# CM5_HighSpeed.net
KiCad netlist of a schematic drawn in Altium Designer
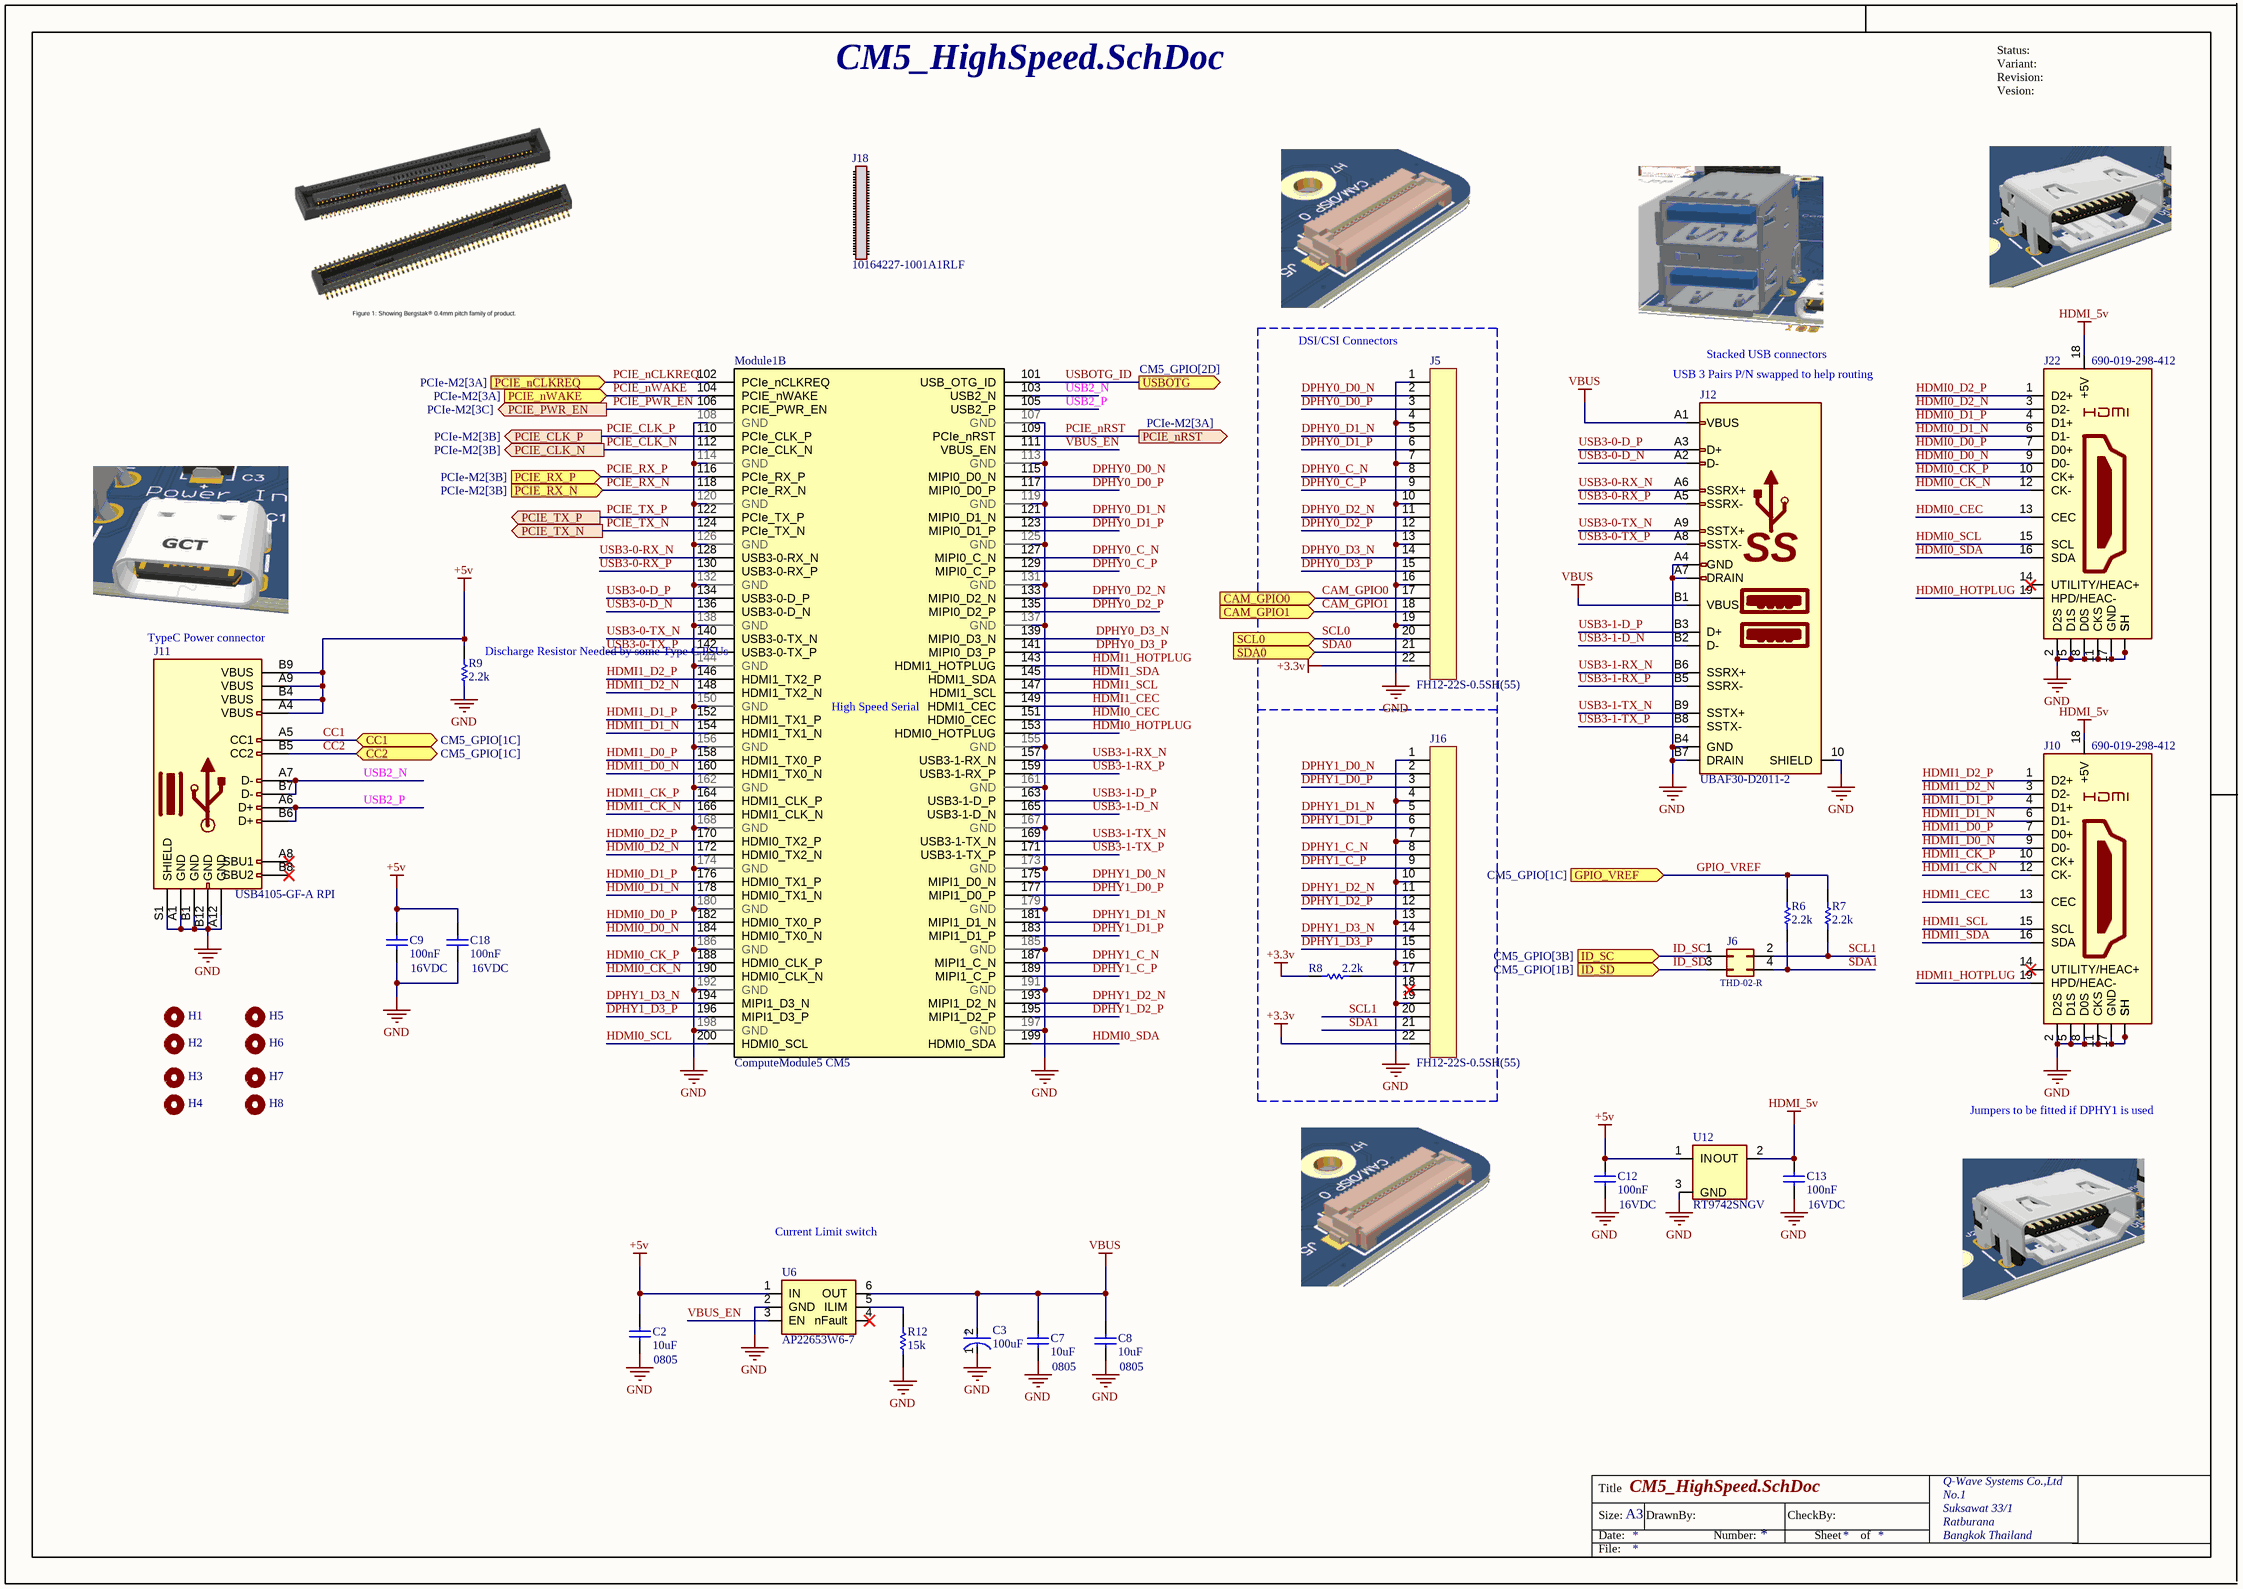
[diagram p0: CM5_HighSpeed.SchDoc]

(export (version "E")
  (design (tool "Eeschema 10.0.6"))
  (components
    (comp (ref "C2")
      (value "10uF")
      (footprint "WCAP-CSGP_0805_H=1.25mm")
      (description "WCAP-CSGP Multilayer Ceramic Chip Capacitor, General Purpose, size 0805, X5R, 10uF, 16V")
      (fields
        (field (name "MANUFACTURER") "Wurth Elektronik")
        (field (name "MANUFACTURER PART NUMBER") "885012107014")
        (field (name "SIZE") "0805")
      )
      (libsource (lib "Q-WAVE SYSTEMS CO") (part "Symbol"))
    )
    (comp (ref "C3")
      (value "100uF")
      (footprint "FP-CX-MFG")
      (description "Cap Aluminum 100uF 6.3V 20% (7.3 X 4.3 X 1.9mm) SMD 0.015 Ohm 2700mA 1000h 105C Embossed T/R")
      (fields (field (name "TOLERANCE") "20%") (field (name "VOLTAGE") "6.3V"))
      (libsource (lib "Q-WAVE SYSTEMS CO") (part "EEF-CX0J101R"))
    )
    (comp (ref "C7")
      (value "10uF")
      (footprint "WCAP-CSGP_0805_H=1.25mm")
      (description "WCAP-CSGP Multilayer Ceramic Chip Capacitor, General Purpose, size 0805, X5R, 10uF, 16V")
      (fields
        (field (name "MANUFACTURER") "Wurth Elektronik")
        (field (name "MANUFACTURER PART NUMBER") "885012107014")
        (field (name "SIZE") "0805")
      )
      (libsource (lib "Q-WAVE SYSTEMS CO") (part "Symbol"))
    )
    (comp (ref "C8")
      (value "10uF")
      (footprint "WCAP-CSGP_0805_H=1.25mm")
      (description "WCAP-CSGP Multilayer Ceramic Chip Capacitor, General Purpose, size 0805, X5R, 10uF, 16V")
      (fields
        (field (name "MANUFACTURER") "Wurth Elektronik")
        (field (name "MANUFACTURER PART NUMBER") "885012107014")
        (field (name "SIZE") "0805")
      )
      (libsource (lib "Q-WAVE SYSTEMS CO") (part "Symbol"))
    )
    (comp (ref "C9")
      (value "100nF")
      (footprint "WCAP-CSGP_0402_H=0.5mm")
      (description "WCAP-CSGP Multilayer Ceramic Chip Capacitor, General Purpose, size 0402, X5R, 100nF, 16V")
      (fields
        (field (name "MANUFACTURER PART NUMBER") "885012105016")
        (field (name "MANUFACTURER") "Wurth Elektronik")
        (field (name "RATED VOLTAGE") "16VDC")
      )
      (libsource (lib "Q-WAVE SYSTEMS CO") (part "Symbol"))
    )
    (comp (ref "C12")
      (value "100nF")
      (footprint "WCAP-CSGP_0402_H=0.5mm")
      (description "WCAP-CSGP Multilayer Ceramic Chip Capacitor, General Purpose, size 0402, X5R, 100nF, 16V")
      (fields
        (field (name "MANUFACTURER PART NUMBER") "885012105016")
        (field (name "MANUFACTURER") "Wurth Elektronik")
        (field (name "RATED VOLTAGE") "16VDC")
      )
      (libsource (lib "Q-WAVE SYSTEMS CO") (part "Symbol"))
    )
    (comp (ref "C13")
      (value "100nF")
      (footprint "WCAP-CSGP_0402_H=0.5mm")
      (description "WCAP-CSGP Multilayer Ceramic Chip Capacitor, General Purpose, size 0402, X5R, 100nF, 16V")
      (fields
        (field (name "MANUFACTURER PART NUMBER") "885012105016")
        (field (name "MANUFACTURER") "Wurth Elektronik")
        (field (name "RATED VOLTAGE") "16VDC")
      )
      (libsource (lib "Q-WAVE SYSTEMS CO") (part "Symbol"))
    )
    (comp (ref "C18")
      (value "100nF")
      (footprint "WCAP-CSGP_0402_H=0.5mm")
      (description "WCAP-CSGP Multilayer Ceramic Chip Capacitor, General Purpose, size 0402, X5R, 100nF, 16V")
      (fields
        (field (name "MANUFACTURER PART NUMBER") "885012105016")
        (field (name "MANUFACTURER") "Wurth Elektronik")
        (field (name "RATED VOLTAGE") "16VDC")
      )
      (libsource (lib "Q-WAVE SYSTEMS CO") (part "Symbol"))
    )
    (comp (ref "H1")
      (value "MountingHole CMIO")
      (footprint "MountingHole CMIO")
      (libsource (lib "Q-WAVE SYSTEMS CO") (part "MountingHole CMIO"))
    )
    (comp (ref "H2")
      (value "MountingHole CMIO")
      (footprint "MountingHole CMIO")
      (libsource (lib "Q-WAVE SYSTEMS CO") (part "MountingHole CMIO"))
    )
    (comp (ref "H3")
      (value "MountingHole CMIO")
      (footprint "MountingHole CMIO")
      (libsource (lib "Q-WAVE SYSTEMS CO") (part "MountingHole CMIO"))
    )
    (comp (ref "H4")
      (value "MountingHole CMIO")
      (footprint "MountingHole CMIO")
      (libsource (lib "Q-WAVE SYSTEMS CO") (part "MountingHole CMIO"))
    )
    (comp (ref "H5")
      (value "MountingHole CMIO")
      (footprint "MountingHole CMIO")
      (libsource (lib "Q-WAVE SYSTEMS CO") (part "MountingHole CMIO"))
    )
    (comp (ref "H6")
      (value "MountingHole CMIO")
      (footprint "MountingHole CMIO")
      (libsource (lib "Q-WAVE SYSTEMS CO") (part "MountingHole CMIO"))
    )
    (comp (ref "H7")
      (value "MountingHole CMIO")
      (footprint "MountingHole CMIO")
      (libsource (lib "Q-WAVE SYSTEMS CO") (part "MountingHole CMIO"))
    )
    (comp (ref "H8")
      (value "MountingHole CMIO")
      (footprint "MountingHole CMIO")
      (libsource (lib "Q-WAVE SYSTEMS CO") (part "MountingHole CMIO"))
    )
    (comp (ref "J5")
      (value "FH12-22S-0.5SH(55)")
      (footprint "FH12-22S-0.5SH(55)")
      (description "Connectors for Connecting - 0.5/1-mm Pitch FPC/FFC - FH12 Series (HIROSE ELECTRIC)")
      (libsource (lib "Q-WAVE SYSTEMS CO") (part "FH12-22S-0.5SH(55)"))
    )
    (comp (ref "J6")
      (value "THD-02-R")
      (footprint "THD-02-R")
      (description "PinHeader 2x02 P2.54mm Vertical")
      (fields
        (field (name "MANUFACTURER") "Wurth Elektronik")
        (field (name "MANUFACTURER PART NUMBER") "61300421121")
      )
      (libsource (lib "Q-WAVE SYSTEMS CO") (part "THD-02-R"))
    )
    (comp (ref "J10")
      (value "690-019-298-412")
      (footprint "690-019-298-412")
      (description "Connector: HDMI; socket; PIN: 19; gold-plated; Body coating: tinned")
      (libsource (lib "Q-WAVE SYSTEMS CO") (part "690-019-298-412"))
    )
    (comp (ref "J11")
      (value "USB4105-GF-A RPI")
      (footprint "USB4105-GF-A RPI")
      (description "Conn USB 2.0 Type C RCP 24 POS 0.3mm/0.5mm Solder RA SMD 24 Terminal 1 Port T/R")
      (libsource (lib "Q-WAVE SYSTEMS CO") (part "USB4105-GF-A RPI"))
    )
    (comp (ref "J12")
      (value "UBAF30-D2011-2")
      (footprint "UBAF30-D2011-2")
      (description "Conn USB 3.0 Type A RCP 18 POS 2mm/2mm Solder RA Thru-Hole 18 Terminal 2 Port T/R")
      (libsource (lib "Q-WAVE SYSTEMS CO") (part "UBAF30-D2011-2"))
    )
    (comp (ref "J16")
      (value "FH12-22S-0.5SH(55)")
      (footprint "FH12-22S-0.5SH(55)")
      (description "Connectors for Connecting - 0.5/1-mm Pitch FPC/FFC - FH12 Series (HIROSE ELECTRIC)")
      (libsource (lib "Q-WAVE SYSTEMS CO") (part "FH12-22S-0.5SH(55)"))
    )
    (comp (ref "J18")
      (value "10164227-1001A1RLF")
      (footprint "CM5-BergStak-10164227")
      (description "CM5 1.5mm Height 0.4MM Btb, 100P, Receptacle, 1.5MM Stack Height")
      (libsource (lib "Q-WAVE SYSTEMS CO") (part "10164227-1001A1RLF"))
    )
    (comp (ref "J22")
      (value "690-019-298-412")
      (footprint "690-019-298-412")
      (description "Connector: HDMI; socket; PIN: 19; gold-plated; Body coating: tinned")
      (libsource (lib "Q-WAVE SYSTEMS CO") (part "690-019-298-412"))
    )
    (comp (ref "Module1")
      (value "ComputeModule5 CM5")
      (footprint "ComputeModule5-CM5")
      (description "Raspberry Pi Compute Module 5")
      (libsource (lib "Q-WAVE SYSTEMS CO") (part "ComputeModule5-CM5"))
    )
    (comp (ref "R6")
      (value "2.2k")
      (footprint "SMD-0402-RES")
      (description "RES SMD 2.2K OHM 1% 1/10W 0402")
      (fields (field (name "TOLERANCE") "±1%") (field (name "PART NUMBER") "ERJ-2RKF2201X"))
      (libsource (lib "Q-WAVE SYSTEMS CO") (part "resistor"))
    )
    (comp (ref "R7")
      (value "2.2k")
      (footprint "SMD-0402-RES")
      (description "RES SMD 2.2K OHM 1% 1/10W 0402")
      (fields (field (name "TOLERANCE") "±1%") (field (name "PART NUMBER") "ERJ-2RKF2201X"))
      (libsource (lib "Q-WAVE SYSTEMS CO") (part "resistor"))
    )
    (comp (ref "R8")
      (value "2.2k")
      (footprint "SMD-0402-RES")
      (description "RES SMD 2.2K OHM 1% 1/10W 0402")
      (fields (field (name "TOLERANCE") "±1%") (field (name "PART NUMBER") "ERJ-2RKF2201X"))
      (libsource (lib "Q-WAVE SYSTEMS CO") (part "resistor"))
    )
    (comp (ref "R9")
      (value "2.2k")
      (footprint "SMD-0402-RES")
      (description "RES SMD 2.2K OHM 1% 1/10W 0402")
      (fields (field (name "TOLERANCE") "±1%") (field (name "PART NUMBER") "ERJ-2RKF2201X"))
      (libsource (lib "Q-WAVE SYSTEMS CO") (part "resistor"))
    )
    (comp (ref "R12")
      (value "15k")
      (footprint "SMD-0402-RES")
      (description "RES SMD 15K OHM 1% 1/10W 0402")
      (fields
        (field (name "DIGI-KEY PART NUMBER") "P15.0KLCT-ND")
        (field (name "PART NUMBER") "ERJ-2RKF1502X")
      )
      (libsource (lib "Q-WAVE SYSTEMS CO") (part "resistor"))
    )
    (comp (ref "U6")
      (value "AP22653W6-7")
      (footprint "FP-SOT26-IPC_A")
      (description "USB Power High Side Switch Single 3V to 5.5V 2.1A 6-Pin SOT-26 T/R")
      (libsource (lib "Q-WAVE SYSTEMS CO") (part "AP22653W6-7"))
    )
    (comp (ref "U12")
      (value "RT9742SNGV")
      (footprint "RT9742SNGV")
      (description "IC Pwr Switch N-chan 1: 1 SOT23-3")
      (libsource (lib "Q-WAVE SYSTEMS CO") (part "RT9742SNGV"))
    )
  )
  (nets
    (net (code "1") (name "+3.3v") (class "Default")
      (node (ref "J16") (pin "22") (pinfunction "Pin_22_22") (pintype "passive"))
      (node (ref "J5") (pin "22") (pinfunction "Pin_22_22") (pintype "passive"))
      (node (ref "R8") (pin "1") (pinfunction "1_1") (pintype "passive"))
    )
    (net (code "2") (name "+5v") (class "Default")
      (node (ref "C12") (pin "2") (pinfunction "2_2") (pintype "passive"))
      (node (ref "C18") (pin "2") (pinfunction "2_2") (pintype "passive"))
      (node (ref "C2") (pin "2") (pinfunction "2_2") (pintype "passive"))
      (node (ref "C9") (pin "2") (pinfunction "2_2") (pintype "passive"))
      (node (ref "J11") (pin "A4") (pinfunction "VBUS_A4") (pintype "passive"))
      (node (ref "J11") (pin "A9") (pinfunction "VBUS_A9") (pintype "passive"))
      (node (ref "J11") (pin "B4") (pinfunction "VBUS_B4") (pintype "passive"))
      (node (ref "J11") (pin "B9") (pinfunction "VBUS_B9") (pintype "passive"))
      (node (ref "R9") (pin "2") (pinfunction "2_2") (pintype "passive"))
      (node (ref "U12") (pin "1") (pinfunction "IN_1") (pintype "passive"))
      (node (ref "U6") (pin "1") (pinfunction "IN_1") (pintype "passive"))
    )
    (net (code "3") (name "/CAM_GPIO0") (class "Default")
      (node (ref "J5") (pin "17") (pinfunction "Pin_17_17") (pintype "passive"))
    )
    (net (code "4") (name "/CAM_GPIO1") (class "Default")
      (node (ref "J5") (pin "18") (pinfunction "Pin_18_18") (pintype "passive"))
    )
    (net (code "5") (name "/CC1") (class "Default")
      (node (ref "J11") (pin "A5") (pinfunction "CC1_A5") (pintype "passive"))
    )
    (net (code "6") (name "/CC2") (class "Default")
      (node (ref "J11") (pin "B5") (pinfunction "CC2_B5") (pintype "passive"))
    )
    (net (code "7") (name "/DPHY0_C_N") (class "Default")
      (node (ref "J5") (pin "8") (pinfunction "Pin_8_8") (pintype "passive"))
      (node (ref "Module1") (pin "127") (pinfunction "MIPI0_C_N_127") (pintype "passive"))
    )
    (net (code "8") (name "/DPHY0_C_P") (class "Default")
      (node (ref "J5") (pin "9") (pinfunction "Pin_9_9") (pintype "passive"))
      (node (ref "Module1") (pin "129") (pinfunction "MIPI0_C_P_129") (pintype "passive"))
    )
    (net (code "9") (name "/DPHY0_D0_N") (class "Default")
      (node (ref "J5") (pin "2") (pinfunction "Pin_2_2") (pintype "passive"))
      (node (ref "Module1") (pin "115") (pinfunction "MIPI0_D0_N_115") (pintype "passive"))
    )
    (net (code "10") (name "/DPHY0_D0_P") (class "Default")
      (node (ref "J5") (pin "3") (pinfunction "Pin_3_3") (pintype "passive"))
      (node (ref "Module1") (pin "117") (pinfunction "MIPI0_D0_P_117") (pintype "passive"))
    )
    (net (code "11") (name "/DPHY0_D1_N") (class "Default")
      (node (ref "J5") (pin "5") (pinfunction "Pin_5_5") (pintype "passive"))
      (node (ref "Module1") (pin "121") (pinfunction "MIPI0_D1_N_121") (pintype "passive"))
    )
    (net (code "12") (name "/DPHY0_D1_P") (class "Default")
      (node (ref "J5") (pin "6") (pinfunction "Pin_6_6") (pintype "passive"))
      (node (ref "Module1") (pin "123") (pinfunction "MIPI0_D1_P_123") (pintype "passive"))
    )
    (net (code "13") (name "/DPHY0_D2_N") (class "Default")
      (node (ref "J5") (pin "11") (pinfunction "Pin_11_11") (pintype "passive"))
      (node (ref "Module1") (pin "133") (pinfunction "MIPI0_D2_N_133") (pintype "passive"))
    )
    (net (code "14") (name "/DPHY0_D2_P") (class "Default")
      (node (ref "J5") (pin "12") (pinfunction "Pin_12_12") (pintype "passive"))
      (node (ref "Module1") (pin "135") (pinfunction "MIPI0_D2_P_135") (pintype "passive"))
    )
    (net (code "15") (name "/DPHY0_D3_N") (class "Default")
      (node (ref "J5") (pin "14") (pinfunction "Pin_14_14") (pintype "passive"))
      (node (ref "Module1") (pin "139") (pinfunction "MIPI0_D3_N_139") (pintype "passive"))
    )
    (net (code "16") (name "/DPHY0_D3_P") (class "Default")
      (node (ref "J5") (pin "15") (pinfunction "Pin_15_15") (pintype "passive"))
      (node (ref "Module1") (pin "141") (pinfunction "MIPI0_D3_P_141") (pintype "passive"))
    )
    (net (code "17") (name "/DPHY1_C_N") (class "Default")
      (node (ref "J16") (pin "8") (pinfunction "Pin_8_8") (pintype "passive"))
      (node (ref "Module1") (pin "187") (pinfunction "MIPI1_C_N_187") (pintype "passive"))
    )
    (net (code "18") (name "/DPHY1_C_P") (class "Default")
      (node (ref "J16") (pin "9") (pinfunction "Pin_9_9") (pintype "passive"))
      (node (ref "Module1") (pin "189") (pinfunction "MIPI1_C_P_189") (pintype "passive"))
    )
    (net (code "19") (name "/DPHY1_D0_N") (class "Default")
      (node (ref "J16") (pin "2") (pinfunction "Pin_2_2") (pintype "passive"))
      (node (ref "Module1") (pin "175") (pinfunction "MIPI1_D0_N_175") (pintype "passive"))
    )
    (net (code "20") (name "/DPHY1_D0_P") (class "Default")
      (node (ref "J16") (pin "3") (pinfunction "Pin_3_3") (pintype "passive"))
      (node (ref "Module1") (pin "177") (pinfunction "MIPI1_D0_P_177") (pintype "passive"))
    )
    (net (code "21") (name "/DPHY1_D1_N") (class "Default")
      (node (ref "J16") (pin "5") (pinfunction "Pin_5_5") (pintype "passive"))
      (node (ref "Module1") (pin "181") (pinfunction "MIPI1_D1_N_181") (pintype "passive"))
    )
    (net (code "22") (name "/DPHY1_D1_P") (class "Default")
      (node (ref "J16") (pin "6") (pinfunction "Pin_6_6") (pintype "passive"))
      (node (ref "Module1") (pin "183") (pinfunction "MIPI1_D1_P_183") (pintype "passive"))
    )
    (net (code "23") (name "/DPHY1_D2_N") (class "Default")
      (node (ref "J16") (pin "11") (pinfunction "Pin_11_11") (pintype "passive"))
      (node (ref "Module1") (pin "193") (pinfunction "MIPI1_D2_N_193") (pintype "passive"))
    )
    (net (code "24") (name "/DPHY1_D2_P") (class "Default")
      (node (ref "J16") (pin "12") (pinfunction "Pin_12_12") (pintype "passive"))
      (node (ref "Module1") (pin "195") (pinfunction "MIPI1_D2_P_195") (pintype "passive"))
    )
    (net (code "25") (name "/DPHY1_D3_N") (class "Default")
      (node (ref "J16") (pin "14") (pinfunction "Pin_14_14") (pintype "passive"))
      (node (ref "Module1") (pin "194") (pinfunction "MIPI1_D3_N_194") (pintype "passive"))
    )
    (net (code "26") (name "/DPHY1_D3_P") (class "Default")
      (node (ref "J16") (pin "15") (pinfunction "Pin_15_15") (pintype "passive"))
      (node (ref "Module1") (pin "196") (pinfunction "MIPI1_D3_P_196") (pintype "passive"))
    )
    (net (code "27") (name "/GPIO_VREF") (class "Default")
      (node (ref "R6") (pin "2") (pinfunction "2_2") (pintype "passive"))
      (node (ref "R7") (pin "2") (pinfunction "2_2") (pintype "passive"))
    )
    (net (code "28") (name "/HDMI0_CEC") (class "Default")
      (node (ref "J22") (pin "13") (pinfunction "CEC_13") (pintype "passive"))
      (node (ref "Module1") (pin "151") (pinfunction "HDMI0_CEC_151") (pintype "passive"))
    )
    (net (code "29") (name "/HDMI0_CK_N") (class "Default")
      (node (ref "J22") (pin "12") (pinfunction "CK-_12") (pintype "passive"))
      (node (ref "Module1") (pin "190") (pinfunction "HDMI0_CLK_N_190") (pintype "passive"))
    )
    (net (code "30") (name "/HDMI0_CK_P") (class "Default")
      (node (ref "J22") (pin "10") (pinfunction "CK+_10") (pintype "passive"))
      (node (ref "Module1") (pin "188") (pinfunction "HDMI0_CLK_P_188") (pintype "passive"))
    )
    (net (code "31") (name "/HDMI0_D0_N") (class "Default")
      (node (ref "J22") (pin "9") (pinfunction "D0-_9") (pintype "passive"))
      (node (ref "Module1") (pin "184") (pinfunction "HDMI0_TX0_N_184") (pintype "passive"))
    )
    (net (code "32") (name "/HDMI0_D0_P") (class "Default")
      (node (ref "J22") (pin "7") (pinfunction "D0+_7") (pintype "passive"))
      (node (ref "Module1") (pin "182") (pinfunction "HDMI0_TX0_P_182") (pintype "passive"))
    )
    (net (code "33") (name "/HDMI0_D1_N") (class "Default")
      (node (ref "J22") (pin "6") (pinfunction "D1-_6") (pintype "passive"))
      (node (ref "Module1") (pin "178") (pinfunction "HDMI0_TX1_N_178") (pintype "passive"))
    )
    (net (code "34") (name "/HDMI0_D1_P") (class "Default")
      (node (ref "J22") (pin "4") (pinfunction "D1+_4") (pintype "passive"))
      (node (ref "Module1") (pin "176") (pinfunction "HDMI0_TX1_P_176") (pintype "passive"))
    )
    (net (code "35") (name "/HDMI0_D2_N") (class "Default")
      (node (ref "J22") (pin "3") (pinfunction "D2-_3") (pintype "passive"))
      (node (ref "Module1") (pin "172") (pinfunction "HDMI0_TX2_N_172") (pintype "passive"))
    )
    (net (code "36") (name "/HDMI0_D2_P") (class "Default")
      (node (ref "J22") (pin "1") (pinfunction "D2+_1") (pintype "passive"))
      (node (ref "Module1") (pin "170") (pinfunction "HDMI0_TX2_P_170") (pintype "passive"))
    )
    (net (code "37") (name "/HDMI0_HOTPLUG") (class "Default")
      (node (ref "J22") (pin "19") (pinfunction "HPD/HEAC-_19") (pintype "passive"))
      (node (ref "Module1") (pin "153") (pinfunction "HDMI0_HOTPLUG_153") (pintype "passive"))
    )
    (net (code "38") (name "/HDMI0_SCL") (class "Default")
      (node (ref "J22") (pin "15") (pinfunction "SCL_15") (pintype "passive"))
      (node (ref "Module1") (pin "200") (pinfunction "HDMI0_SCL_200") (pintype "passive"))
    )
    (net (code "39") (name "/HDMI0_SDA") (class "Default")
      (node (ref "J22") (pin "16") (pinfunction "SDA_16") (pintype "passive"))
      (node (ref "Module1") (pin "199") (pinfunction "HDMI0_SDA_199") (pintype "passive"))
    )
    (net (code "40") (name "/HDMI1_CEC") (class "Default")
      (node (ref "J10") (pin "13") (pinfunction "CEC_13") (pintype "passive"))
      (node (ref "Module1") (pin "149") (pinfunction "HDMI1_CEC_149") (pintype "passive"))
    )
    (net (code "41") (name "/HDMI1_CK_N") (class "Default")
      (node (ref "J10") (pin "12") (pinfunction "CK-_12") (pintype "passive"))
      (node (ref "Module1") (pin "166") (pinfunction "HDMI1_CLK_N_166") (pintype "passive"))
    )
    (net (code "42") (name "/HDMI1_CK_P") (class "Default")
      (node (ref "J10") (pin "10") (pinfunction "CK+_10") (pintype "passive"))
      (node (ref "Module1") (pin "164") (pinfunction "HDMI1_CLK_P_164") (pintype "passive"))
    )
    (net (code "43") (name "/HDMI1_D0_N") (class "Default")
      (node (ref "J10") (pin "9") (pinfunction "D0-_9") (pintype "passive"))
      (node (ref "Module1") (pin "160") (pinfunction "HDMI1_TX0_N_160") (pintype "passive"))
    )
    (net (code "44") (name "/HDMI1_D0_P") (class "Default")
      (node (ref "J10") (pin "7") (pinfunction "D0+_7") (pintype "passive"))
      (node (ref "Module1") (pin "158") (pinfunction "HDMI1_TX0_P_158") (pintype "passive"))
    )
    (net (code "45") (name "/HDMI1_D1_N") (class "Default")
      (node (ref "J10") (pin "6") (pinfunction "D1-_6") (pintype "passive"))
      (node (ref "Module1") (pin "154") (pinfunction "HDMI1_TX1_N_154") (pintype "passive"))
    )
    (net (code "46") (name "/HDMI1_D1_P") (class "Default")
      (node (ref "J10") (pin "4") (pinfunction "D1+_4") (pintype "passive"))
      (node (ref "Module1") (pin "152") (pinfunction "HDMI1_TX1_P_152") (pintype "passive"))
    )
    (net (code "47") (name "/HDMI1_D2_N") (class "Default")
      (node (ref "J10") (pin "3") (pinfunction "D2-_3") (pintype "passive"))
      (node (ref "Module1") (pin "148") (pinfunction "HDMI1_TX2_N_148") (pintype "passive"))
    )
    (net (code "48") (name "/HDMI1_D2_P") (class "Default")
      (node (ref "J10") (pin "1") (pinfunction "D2+_1") (pintype "passive"))
      (node (ref "Module1") (pin "146") (pinfunction "HDMI1_TX2_P_146") (pintype "passive"))
    )
    (net (code "49") (name "/HDMI1_HOTPLUG") (class "Default")
      (node (ref "J10") (pin "19") (pinfunction "HPD/HEAC-_19") (pintype "passive"))
      (node (ref "Module1") (pin "143") (pinfunction "HDMI1_HOTPLUG_143") (pintype "passive"))
    )
    (net (code "50") (name "/HDMI1_SCL") (class "Default")
      (node (ref "J10") (pin "15") (pinfunction "SCL_15") (pintype "passive"))
      (node (ref "Module1") (pin "147") (pinfunction "HDMI1_SCL_147") (pintype "passive"))
    )
    (net (code "51") (name "/HDMI1_SDA") (class "Default")
      (node (ref "J10") (pin "16") (pinfunction "SDA_16") (pintype "passive"))
      (node (ref "Module1") (pin "145") (pinfunction "HDMI1_SDA_145") (pintype "passive"))
    )
    (net (code "52") (name "/ID_SC") (class "Default")
      (node (ref "J6") (pin "1") (pinfunction "Pin_1_1") (pintype "passive"))
    )
    (net (code "53") (name "/ID_SD") (class "Default")
      (node (ref "J6") (pin "3") (pinfunction "Pin_3_3") (pintype "passive"))
    )
    (net (code "54") (name "/PCIE_CLK_N") (class "Default")
      (node (ref "Module1") (pin "112") (pinfunction "PCIe_CLK_N_112") (pintype "passive"))
    )
    (net (code "55") (name "/PCIE_CLK_P") (class "Default")
      (node (ref "Module1") (pin "110") (pinfunction "PCIe_CLK_P_110") (pintype "passive"))
    )
    (net (code "56") (name "/PCIE_PWR_EN") (class "Default")
      (node (ref "Module1") (pin "106") (pinfunction "PCIE_PWR_EN_106") (pintype "passive"))
    )
    (net (code "57") (name "/PCIE_RX_N") (class "Default")
      (node (ref "Module1") (pin "118") (pinfunction "PCIe_RX_N_118") (pintype "passive"))
    )
    (net (code "58") (name "/PCIE_RX_P") (class "Default")
      (node (ref "Module1") (pin "116") (pinfunction "PCIe_RX_P_116") (pintype "passive"))
    )
    (net (code "59") (name "/PCIE_TX_N") (class "Default")
      (node (ref "Module1") (pin "124") (pinfunction "PCIe_TX_N_124") (pintype "passive"))
    )
    (net (code "60") (name "/PCIE_TX_P") (class "Default")
      (node (ref "Module1") (pin "122") (pinfunction "PCIe_TX_P_122") (pintype "passive"))
    )
    (net (code "61") (name "/PCIE_nCLKREQ") (class "Default")
      (node (ref "Module1") (pin "102") (pinfunction "PCIe_nCLKREQ_102") (pintype "passive"))
    )
    (net (code "62") (name "/PCIE_nRST") (class "Default")
      (node (ref "Module1") (pin "109") (pinfunction "PCIe_nRST_109") (pintype "passive"))
    )
    (net (code "63") (name "/PCIE_nWAKE") (class "Default")
      (node (ref "Module1") (pin "104") (pinfunction "PCIE_nWAKE_104") (pintype "passive"))
    )
    (net (code "64") (name "/SCL0") (class "Default")
      (node (ref "J5") (pin "20") (pinfunction "Pin_20_20") (pintype "passive"))
    )
    (net (code "65") (name "/SCL1") (class "Default")
      (node (ref "J16") (pin "20") (pinfunction "Pin_20_20") (pintype "passive"))
      (node (ref "J6") (pin "2") (pinfunction "Pin_2_2") (pintype "passive"))
      (node (ref "R7") (pin "1") (pinfunction "1_1") (pintype "passive"))
    )
    (net (code "66") (name "/SDA0") (class "Default")
      (node (ref "J5") (pin "21") (pinfunction "Pin_21_21") (pintype "passive"))
    )
    (net (code "67") (name "/SDA1") (class "Default")
      (node (ref "J16") (pin "21") (pinfunction "Pin_21_21") (pintype "passive"))
      (node (ref "J6") (pin "4") (pinfunction "Pin_4_4") (pintype "passive"))
      (node (ref "R6") (pin "1") (pinfunction "1_1") (pintype "passive"))
    )
    (net (code "68") (name "/USB2_N") (class "Default")
      (node (ref "J11") (pin "A7") (pinfunction "D-_A7") (pintype "passive"))
      (node (ref "J11") (pin "B7") (pinfunction "D-_B7") (pintype "passive"))
      (node (ref "Module1") (pin "103") (pinfunction "USB2_N_103") (pintype "passive"))
    )
    (net (code "69") (name "/USB2_P") (class "Default")
      (node (ref "J11") (pin "A6") (pinfunction "D+_A6") (pintype "passive"))
      (node (ref "J11") (pin "B6") (pinfunction "D+_B6") (pintype "passive"))
      (node (ref "Module1") (pin "105") (pinfunction "USB2_P_105") (pintype "passive"))
    )
    (net (code "70") (name "/USB3-0-D_N") (class "Default")
      (node (ref "J12") (pin "A2") (pinfunction "D-_A2") (pintype "passive"))
      (node (ref "Module1") (pin "136") (pinfunction "USB3-0-D_N_136") (pintype "passive"))
    )
    (net (code "71") (name "/USB3-0-D_P") (class "Default")
      (node (ref "J12") (pin "A3") (pinfunction "D+_A3") (pintype "passive"))
      (node (ref "Module1") (pin "134") (pinfunction "USB3-0-D_P_134") (pintype "passive"))
    )
    (net (code "72") (name "/USB3-0-RX_N") (class "Default")
      (node (ref "J12") (pin "A6") (pinfunction "SSRX+_A6") (pintype "passive"))
      (node (ref "Module1") (pin "128") (pinfunction "USB3-0-RX_N_128") (pintype "passive"))
    )
    (net (code "73") (name "/USB3-0-RX_P") (class "Default")
      (node (ref "J12") (pin "A5") (pinfunction "SSRX-_A5") (pintype "passive"))
      (node (ref "Module1") (pin "130") (pinfunction "USB3-0-RX_P_130") (pintype "passive"))
    )
    (net (code "74") (name "/USB3-0-TX_N") (class "Default")
      (node (ref "J12") (pin "A9") (pinfunction "SSTX+_A9") (pintype "passive"))
      (node (ref "Module1") (pin "140") (pinfunction "USB3-0-TX_N_140") (pintype "passive"))
    )
    (net (code "75") (name "/USB3-0-TX_P") (class "Default")
      (node (ref "J12") (pin "A8") (pinfunction "SSTX-_A8") (pintype "passive"))
      (node (ref "Module1") (pin "142") (pinfunction "USB3-0-TX_P_142") (pintype "passive"))
    )
    (net (code "76") (name "/USB3-1-D_N") (class "Default")
      (node (ref "J12") (pin "B2") (pinfunction "D-_B2") (pintype "passive"))
      (node (ref "Module1") (pin "165") (pinfunction "USB3-1-D_N_165") (pintype "passive"))
    )
    (net (code "77") (name "/USB3-1-D_P") (class "Default")
      (node (ref "J12") (pin "B3") (pinfunction "D+_B3") (pintype "passive"))
      (node (ref "Module1") (pin "163") (pinfunction "USB3-1-D_P_163") (pintype "passive"))
    )
    (net (code "78") (name "/USB3-1-RX_N") (class "Default")
      (node (ref "J12") (pin "B6") (pinfunction "SSRX+_B6") (pintype "passive"))
      (node (ref "Module1") (pin "157") (pinfunction "USB3-1-RX_N_157") (pintype "passive"))
    )
    (net (code "79") (name "/USB3-1-RX_P") (class "Default")
      (node (ref "J12") (pin "B5") (pinfunction "SSRX-_B5") (pintype "passive"))
      (node (ref "Module1") (pin "159") (pinfunction "USB3-1-RX_P_159") (pintype "passive"))
    )
    (net (code "80") (name "/USB3-1-TX_N") (class "Default")
      (node (ref "J12") (pin "B9") (pinfunction "SSTX+_B9") (pintype "passive"))
      (node (ref "Module1") (pin "169") (pinfunction "USB3-1-TX_N_169") (pintype "passive"))
    )
    (net (code "81") (name "/USB3-1-TX_P") (class "Default")
      (node (ref "J12") (pin "B8") (pinfunction "SSTX-_B8") (pintype "passive"))
      (node (ref "Module1") (pin "171") (pinfunction "USB3-1-TX_P_171") (pintype "passive"))
    )
    (net (code "82") (name "/USBOTG_ID") (class "Default")
      (node (ref "Module1") (pin "101") (pinfunction "USB_OTG_ID_101") (pintype "passive"))
    )
    (net (code "83") (name "/VBUS_EN") (class "Default")
      (node (ref "Module1") (pin "111") (pinfunction "VBUS_EN_111") (pintype "passive"))
      (node (ref "U6") (pin "3") (pinfunction "EN_3") (pintype "passive"))
    )
    (net (code "84") (name "GND") (class "Default")
      (node (ref "C12") (pin "1") (pinfunction "1_1") (pintype "passive"))
      (node (ref "C13") (pin "1") (pinfunction "1_1") (pintype "passive"))
      (node (ref "C18") (pin "1") (pinfunction "1_1") (pintype "passive"))
      (node (ref "C2") (pin "1") (pinfunction "1_1") (pintype "passive"))
      (node (ref "C3") (pin "1") (pinfunction "C_1") (pintype "passive"))
      (node (ref "C7") (pin "1") (pinfunction "1_1") (pintype "passive"))
      (node (ref "C8") (pin "1") (pinfunction "1_1") (pintype "passive"))
      (node (ref "C9") (pin "1") (pinfunction "1_1") (pintype "passive"))
      (node (ref "J10") (pin "11") (pinfunction "CKS_11") (pintype "passive"))
      (node (ref "J10") (pin "17") (pinfunction "GND_17") (pintype "passive"))
      (node (ref "J10") (pin "2") (pinfunction "D2S_2") (pintype "passive"))
      (node (ref "J10") (pin "5") (pinfunction "D1S_5") (pintype "passive"))
      (node (ref "J10") (pin "8") (pinfunction "D0S_8") (pintype "passive"))
      (node (ref "J10") (pin "SH1") (pinfunction "SH_SH1") (pintype "passive"))
      (node (ref "J10") (pin "SH2") (pinfunction "SH_SH2") (pintype "passive"))
      (node (ref "J10") (pin "SH3") (pinfunction "SH_SH3") (pintype "passive"))
      (node (ref "J10") (pin "SH4") (pinfunction "SH_SH4") (pintype "passive"))
      (node (ref "J11") (pin "A1") (pinfunction "GND_A1") (pintype "passive"))
      (node (ref "J11") (pin "A12") (pinfunction "GND_A12") (pintype "passive"))
      (node (ref "J11") (pin "B1") (pinfunction "GND_B1") (pintype "passive"))
      (node (ref "J11") (pin "B12") (pinfunction "GND_B12") (pintype "passive"))
      (node (ref "J11") (pin "S1") (pinfunction "SHIELD_S1") (pintype "passive"))
      (node (ref "J12") (pin "10") (pinfunction "SHIELD_10") (pintype "passive"))
      (node (ref "J12") (pin "A4") (pinfunction "GND_A4") (pintype "passive"))
      (node (ref "J12") (pin "A7") (pinfunction "DRAIN_A7") (pintype "passive"))
      (node (ref "J12") (pin "B4") (pinfunction "GND_B4") (pintype "passive"))
      (node (ref "J12") (pin "B7") (pinfunction "DRAIN_B7") (pintype "passive"))
      (node (ref "J16") (pin "1") (pinfunction "Pin_1_1") (pintype "passive"))
      (node (ref "J16") (pin "10") (pinfunction "Pin_10_10") (pintype "passive"))
      (node (ref "J16") (pin "13") (pinfunction "Pin_13_13") (pintype "passive"))
      (node (ref "J16") (pin "16") (pinfunction "Pin_16_16") (pintype "passive"))
      (node (ref "J16") (pin "19") (pinfunction "Pin_19_19") (pintype "passive"))
      (node (ref "J16") (pin "4") (pinfunction "Pin_4_4") (pintype "passive"))
      (node (ref "J16") (pin "7") (pinfunction "Pin_7_7") (pintype "passive"))
      (node (ref "J22") (pin "11") (pinfunction "CKS_11") (pintype "passive"))
      (node (ref "J22") (pin "17") (pinfunction "GND_17") (pintype "passive"))
      (node (ref "J22") (pin "2") (pinfunction "D2S_2") (pintype "passive"))
      (node (ref "J22") (pin "5") (pinfunction "D1S_5") (pintype "passive"))
      (node (ref "J22") (pin "8") (pinfunction "D0S_8") (pintype "passive"))
      (node (ref "J22") (pin "SH1") (pinfunction "SH_SH1") (pintype "passive"))
      (node (ref "J22") (pin "SH2") (pinfunction "SH_SH2") (pintype "passive"))
      (node (ref "J22") (pin "SH3") (pinfunction "SH_SH3") (pintype "passive"))
      (node (ref "J22") (pin "SH4") (pinfunction "SH_SH4") (pintype "passive"))
      (node (ref "J5") (pin "1") (pinfunction "Pin_1_1") (pintype "passive"))
      (node (ref "J5") (pin "10") (pinfunction "Pin_10_10") (pintype "passive"))
      (node (ref "J5") (pin "13") (pinfunction "Pin_13_13") (pintype "passive"))
      (node (ref "J5") (pin "16") (pinfunction "Pin_16_16") (pintype "passive"))
      (node (ref "J5") (pin "19") (pinfunction "Pin_19_19") (pintype "passive"))
      (node (ref "J5") (pin "4") (pinfunction "Pin_4_4") (pintype "passive"))
      (node (ref "J5") (pin "7") (pinfunction "Pin_7_7") (pintype "passive"))
      (node (ref "Module1") (pin "107") (pinfunction "GND_107") (pintype "passive"))
      (node (ref "Module1") (pin "108") (pinfunction "GND_108") (pintype "passive"))
      (node (ref "Module1") (pin "113") (pinfunction "GND_113") (pintype "passive"))
      (node (ref "Module1") (pin "114") (pinfunction "GND_114") (pintype "passive"))
      (node (ref "Module1") (pin "119") (pinfunction "GND_119") (pintype "passive"))
      (node (ref "Module1") (pin "120") (pinfunction "GND_120") (pintype "passive"))
      (node (ref "Module1") (pin "125") (pinfunction "GND_125") (pintype "passive"))
      (node (ref "Module1") (pin "126") (pinfunction "GND_126") (pintype "passive"))
      (node (ref "Module1") (pin "131") (pinfunction "GND_131") (pintype "passive"))
      (node (ref "Module1") (pin "132") (pinfunction "GND_132") (pintype "passive"))
      (node (ref "Module1") (pin "137") (pinfunction "GND_137") (pintype "passive"))
      (node (ref "Module1") (pin "138") (pinfunction "GND_138") (pintype "passive"))
      (node (ref "Module1") (pin "144") (pinfunction "GND_144") (pintype "passive"))
      (node (ref "Module1") (pin "150") (pinfunction "GND_150") (pintype "passive"))
      (node (ref "Module1") (pin "155") (pinfunction "GND_155") (pintype "passive"))
      (node (ref "Module1") (pin "156") (pinfunction "GND_156") (pintype "passive"))
      (node (ref "Module1") (pin "161") (pinfunction "GND_161") (pintype "passive"))
      (node (ref "Module1") (pin "162") (pinfunction "GND_162") (pintype "passive"))
      (node (ref "Module1") (pin "167") (pinfunction "GND_167") (pintype "passive"))
      (node (ref "Module1") (pin "168") (pinfunction "GND_168") (pintype "passive"))
      (node (ref "Module1") (pin "173") (pinfunction "GND_173") (pintype "passive"))
      (node (ref "Module1") (pin "174") (pinfunction "GND_174") (pintype "passive"))
      (node (ref "Module1") (pin "179") (pinfunction "GND_179") (pintype "passive"))
      (node (ref "Module1") (pin "180") (pinfunction "GND_180") (pintype "passive"))
      (node (ref "Module1") (pin "185") (pinfunction "GND_185") (pintype "passive"))
      (node (ref "Module1") (pin "186") (pinfunction "GND_186") (pintype "passive"))
      (node (ref "Module1") (pin "191") (pinfunction "GND_191") (pintype "passive"))
      (node (ref "Module1") (pin "192") (pinfunction "GND_192") (pintype "passive"))
      (node (ref "Module1") (pin "197") (pinfunction "GND_197") (pintype "passive"))
      (node (ref "Module1") (pin "198") (pinfunction "GND_198") (pintype "passive"))
      (node (ref "R12") (pin "2") (pinfunction "2_2") (pintype "passive"))
      (node (ref "R9") (pin "1") (pinfunction "1_1") (pintype "passive"))
      (node (ref "U12") (pin "3") (pinfunction "GND_3") (pintype "passive"))
      (node (ref "U6") (pin "2") (pinfunction "GND_2") (pintype "passive"))
    )
    (net (code "85") (name "HDMI_5v") (class "Default")
      (node (ref "C13") (pin "2") (pinfunction "2_2") (pintype "passive"))
      (node (ref "J10") (pin "18") (pinfunction "+5V_18") (pintype "passive"))
      (node (ref "J22") (pin "18") (pinfunction "+5V_18") (pintype "passive"))
      (node (ref "U12") (pin "2") (pinfunction "OUT_2") (pintype "passive"))
    )
    (net (code "86") (name "Net-(J16-Pin_17)") (class "Default")
      (node (ref "J16") (pin "17") (pinfunction "Pin_17_17") (pintype "passive"))
      (node (ref "R8") (pin "2") (pinfunction "2_2") (pintype "passive"))
    )
    (net (code "87") (name "Net-(U6-ILIM)") (class "Default")
      (node (ref "R12") (pin "1") (pinfunction "1_1") (pintype "passive"))
      (node (ref "U6") (pin "5") (pinfunction "ILIM_5") (pintype "passive"))
    )
    (net (code "88") (name "VBUS") (class "Default")
      (node (ref "C3") (pin "2") (pinfunction "A_2") (pintype "passive"))
      (node (ref "C7") (pin "2") (pinfunction "2_2") (pintype "passive"))
      (node (ref "C8") (pin "2") (pinfunction "2_2") (pintype "passive"))
      (node (ref "J12") (pin "A1") (pinfunction "VBUS_A1") (pintype "passive"))
      (node (ref "J12") (pin "B1") (pinfunction "VBUS_B1") (pintype "passive"))
      (node (ref "U6") (pin "6") (pinfunction "OUT_6") (pintype "passive"))
    )
    (net (code "89") (name "unconnected-(J10-UTILITY{slash}HEAC+-Pad14)") (class "Default")
      (node (ref "J10") (pin "14") (pinfunction "UTILITY/HEAC+_14") (pintype "passive+no_connect"))
    )
    (net (code "90") (name "unconnected-(J11-SBU1-PadA8)") (class "Default")
      (node (ref "J11") (pin "A8") (pinfunction "SBU1_A8") (pintype "passive+no_connect"))
    )
    (net (code "91") (name "unconnected-(J11-SBU2-PadB8)") (class "Default")
      (node (ref "J11") (pin "B8") (pinfunction "SBU2_B8") (pintype "passive+no_connect"))
    )
    (net (code "92") (name "unconnected-(J16-Pin_18-Pad18)") (class "Default")
      (node (ref "J16") (pin "18") (pinfunction "Pin_18_18") (pintype "passive+no_connect"))
    )
    (net (code "93") (name "unconnected-(J22-UTILITY{slash}HEAC+-Pad14)") (class "Default")
      (node (ref "J22") (pin "14") (pinfunction "UTILITY/HEAC+_14") (pintype "passive+no_connect"))
    )
    (net (code "94") (name "unconnected-(U6-nFault-Pad4)") (class "Default")
      (node (ref "U6") (pin "4") (pinfunction "nFault_4") (pintype "passive+no_connect"))
    )
  )
)
